# USB-to-Quad-RS-485-Conv-Module.net
KiCad netlist of a schematic drawn in EAGLE
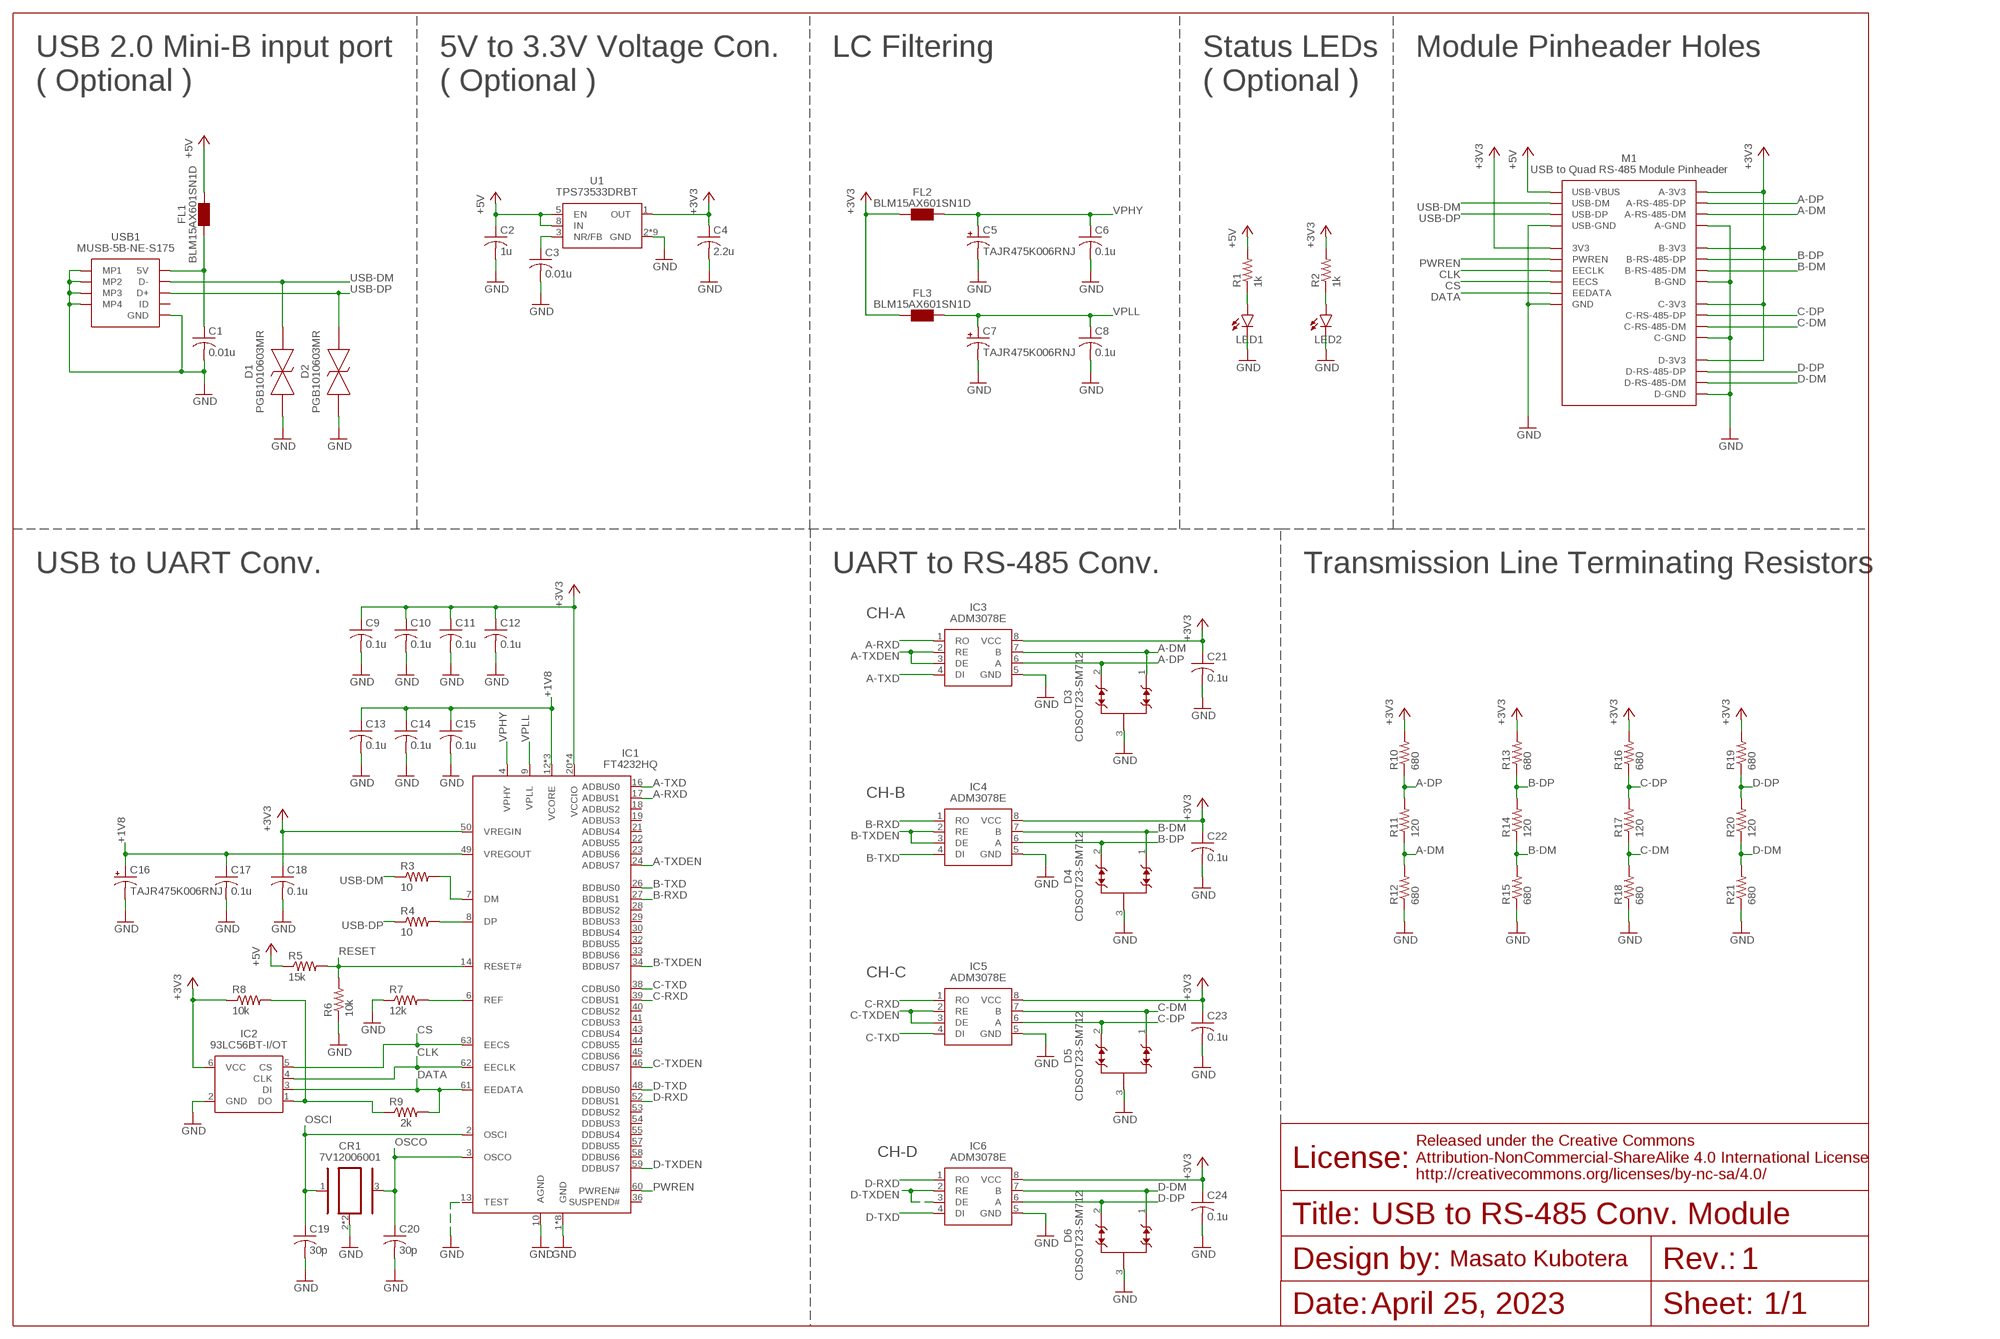
[diagram p0: schematic, sheet 1]

(export (version "E")
  (design (tool "Eeschema 10.0.6"))
  (components
    (comp (ref "C1")
      (value "0.01u")
      (footprint "eagle-import:C0402")
      (libsource (lib "eagle-import") (part "C-USC0402"))
    )
    (comp (ref "C2")
      (value "1u")
      (footprint "eagle-import:C0402")
      (libsource (lib "eagle-import") (part "C-USC0402"))
    )
    (comp (ref "C3")
      (value "0.01u")
      (footprint "eagle-import:C0402")
      (libsource (lib "eagle-import") (part "C-USC0402"))
    )
    (comp (ref "C4")
      (value "2.2u")
      (footprint "eagle-import:C0402")
      (libsource (lib "eagle-import") (part "C-USC0402"))
    )
    (comp (ref "C5")
      (value "4.7u")
      (footprint "eagle-import:0805K")
      (libsource (lib "eagle-import") (part "TAJR475K006RNJ"))
    )
    (comp (ref "C6")
      (value "0.1u")
      (footprint "eagle-import:C0402")
      (libsource (lib "eagle-import") (part "C-USC0402"))
    )
    (comp (ref "C7")
      (value "4.7u")
      (footprint "eagle-import:0805K")
      (libsource (lib "eagle-import") (part "TAJR475K006RNJ"))
    )
    (comp (ref "C8")
      (value "0.1u")
      (footprint "eagle-import:C0402")
      (libsource (lib "eagle-import") (part "C-USC0402"))
    )
    (comp (ref "C9")
      (value "0.1u")
      (footprint "eagle-import:C0402")
      (libsource (lib "eagle-import") (part "C-USC0402"))
    )
    (comp (ref "C10")
      (value "0.1u")
      (footprint "eagle-import:C0402")
      (libsource (lib "eagle-import") (part "C-USC0402"))
    )
    (comp (ref "C11")
      (value "0.1u")
      (footprint "eagle-import:C0402")
      (libsource (lib "eagle-import") (part "C-USC0402"))
    )
    (comp (ref "C12")
      (value "0.1u")
      (footprint "eagle-import:C0402")
      (libsource (lib "eagle-import") (part "C-USC0402"))
    )
    (comp (ref "C13")
      (value "0.1u")
      (footprint "eagle-import:C0402")
      (libsource (lib "eagle-import") (part "C-USC0402"))
    )
    (comp (ref "C14")
      (value "0.1u")
      (footprint "eagle-import:C0402")
      (libsource (lib "eagle-import") (part "C-USC0402"))
    )
    (comp (ref "C15")
      (value "0.1u")
      (footprint "eagle-import:C0402")
      (libsource (lib "eagle-import") (part "C-USC0402"))
    )
    (comp (ref "C16")
      (value "4.7u")
      (footprint "eagle-import:0805K")
      (libsource (lib "eagle-import") (part "TAJR475K006RNJ"))
    )
    (comp (ref "C17")
      (value "0.1u")
      (footprint "eagle-import:C0402")
      (libsource (lib "eagle-import") (part "C-USC0402"))
    )
    (comp (ref "C18")
      (value "0.1u")
      (footprint "eagle-import:C0402")
      (libsource (lib "eagle-import") (part "C-USC0402"))
    )
    (comp (ref "C19")
      (value "30p")
      (footprint "eagle-import:C0402")
      (libsource (lib "eagle-import") (part "C-USC0402"))
    )
    (comp (ref "C20")
      (value "30p")
      (footprint "eagle-import:C0402")
      (libsource (lib "eagle-import") (part "C-USC0402"))
    )
    (comp (ref "C21")
      (value "0.1u")
      (footprint "eagle-import:C0402")
      (libsource (lib "eagle-import") (part "C-USC0402"))
    )
    (comp (ref "C22")
      (value "0.1u")
      (footprint "eagle-import:C0402")
      (libsource (lib "eagle-import") (part "C-USC0402"))
    )
    (comp (ref "C23")
      (value "0.1u")
      (footprint "eagle-import:C0402")
      (libsource (lib "eagle-import") (part "C-USC0402"))
    )
    (comp (ref "C24")
      (value "0.1u")
      (footprint "eagle-import:C0402")
      (libsource (lib "eagle-import") (part "C-USC0402"))
    )
    (comp (ref "CR1")
      (value "7V12006001")
      (footprint "eagle-import:7V12006001")
      (libsource (lib "eagle-import") (part "7V12006001"))
    )
    (comp (ref "D1")
      (value "PGB1010603MR")
      (footprint "eagle-import:0603")
      (libsource (lib "eagle-import") (part "PGB1010603MR"))
    )
    (comp (ref "D2")
      (value "PGB1010603MR")
      (footprint "eagle-import:0603")
      (libsource (lib "eagle-import") (part "PGB1010603MR"))
    )
    (comp (ref "D3")
      (value "CDSOT23-SM712")
      (footprint "eagle-import:SOT-23-3")
      (libsource (lib "eagle-import") (part "CDSOT23-SM712"))
    )
    (comp (ref "D4")
      (value "CDSOT23-SM712")
      (footprint "eagle-import:SOT-23-3")
      (libsource (lib "eagle-import") (part "CDSOT23-SM712"))
    )
    (comp (ref "D5")
      (value "CDSOT23-SM712")
      (footprint "eagle-import:SOT-23-3")
      (libsource (lib "eagle-import") (part "CDSOT23-SM712"))
    )
    (comp (ref "D6")
      (value "CDSOT23-SM712")
      (footprint "eagle-import:SOT-23-3")
      (libsource (lib "eagle-import") (part "CDSOT23-SM712"))
    )
    (comp (ref "FL1")
      (value "BLM15AX601SN1D")
      (footprint "eagle-import:BLM15AX601SN1D")
      (libsource (lib "eagle-import") (part "BLM15AX601SN1D"))
    )
    (comp (ref "FL2")
      (value "BLM15AX601SN1D")
      (footprint "eagle-import:BLM15AX601SN1D")
      (libsource (lib "eagle-import") (part "BLM15AX601SN1D"))
    )
    (comp (ref "FL3")
      (value "BLM15AX601SN1D")
      (footprint "eagle-import:BLM15AX601SN1D")
      (libsource (lib "eagle-import") (part "BLM15AX601SN1D"))
    )
    (comp (ref "IC1")
      (value "FT4232HQ")
      (footprint "eagle-import:FT4232HQ")
      (libsource (lib "eagle-import") (part "FT4232HQ"))
    )
    (comp (ref "IC2")
      (value "93LC56BT-I/OT")
      (footprint "eagle-import:SOT-23-6")
      (libsource (lib "eagle-import") (part "93LC56BT-I/OT"))
    )
    (comp (ref "IC3")
      (value "ADM3078E")
      (footprint "eagle-import:SOIC-8")
      (libsource (lib "eagle-import") (part "ADM3078E"))
    )
    (comp (ref "IC4")
      (value "ADM3078E")
      (footprint "eagle-import:SOIC-8")
      (libsource (lib "eagle-import") (part "ADM3078E"))
    )
    (comp (ref "IC5")
      (value "ADM3078E")
      (footprint "eagle-import:SOIC-8")
      (libsource (lib "eagle-import") (part "ADM3078E"))
    )
    (comp (ref "IC6")
      (value "ADM3078E")
      (footprint "eagle-import:SOIC-8")
      (libsource (lib "eagle-import") (part "ADM3078E"))
    )
    (comp (ref "LED1")
      (value "LEDSML0603")
      (footprint "eagle-import:SML0603")
      (libsource (lib "eagle-import") (part "LEDSML0603"))
    )
    (comp (ref "LED2")
      (value "LEDSML0603")
      (footprint "eagle-import:SML0603")
      (libsource (lib "eagle-import") (part "LEDSML0603"))
    )
    (comp (ref "M1")
      (value "USB-TO-QUAD-RS-485-CONV-MODULE")
      (footprint "eagle-import:USB-TO-QUAD-RS-485-CONV-MODULE-DIMENSION")
      (libsource (lib "eagle-import") (part "USB-TO-QUAD-RS-485-CONV-MODULE"))
    )
    (comp (ref "R1")
      (value "1k")
      (footprint "eagle-import:R0402")
      (libsource (lib "eagle-import") (part "R-US_R0402"))
    )
    (comp (ref "R2")
      (value "1k")
      (footprint "eagle-import:R0402")
      (libsource (lib "eagle-import") (part "R-US_R0402"))
    )
    (comp (ref "R3")
      (value "10")
      (footprint "eagle-import:R0402")
      (libsource (lib "eagle-import") (part "R-US_R0402"))
    )
    (comp (ref "R4")
      (value "10")
      (footprint "eagle-import:R0402")
      (libsource (lib "eagle-import") (part "R-US_R0402"))
    )
    (comp (ref "R5")
      (value "15k")
      (footprint "eagle-import:R0402")
      (libsource (lib "eagle-import") (part "R-US_R0402"))
    )
    (comp (ref "R6")
      (value "10k")
      (footprint "eagle-import:R0402")
      (libsource (lib "eagle-import") (part "R-US_R0402"))
    )
    (comp (ref "R7")
      (value "12k")
      (footprint "eagle-import:R0402")
      (libsource (lib "eagle-import") (part "R-US_R0402"))
    )
    (comp (ref "R8")
      (value "10k")
      (footprint "eagle-import:R0402")
      (libsource (lib "eagle-import") (part "R-US_R0402"))
    )
    (comp (ref "R9")
      (value "2k")
      (footprint "eagle-import:R0402")
      (libsource (lib "eagle-import") (part "R-US_R0402"))
    )
    (comp (ref "R10")
      (value "680")
      (footprint "eagle-import:R0402")
      (libsource (lib "eagle-import") (part "R-US_R0402"))
    )
    (comp (ref "R11")
      (value "120")
      (footprint "eagle-import:R0402")
      (libsource (lib "eagle-import") (part "R-US_R0402"))
    )
    (comp (ref "R12")
      (value "680")
      (footprint "eagle-import:R0402")
      (libsource (lib "eagle-import") (part "R-US_R0402"))
    )
    (comp (ref "R13")
      (value "680")
      (footprint "eagle-import:R0402")
      (libsource (lib "eagle-import") (part "R-US_R0402"))
    )
    (comp (ref "R14")
      (value "120")
      (footprint "eagle-import:R0402")
      (libsource (lib "eagle-import") (part "R-US_R0402"))
    )
    (comp (ref "R15")
      (value "680")
      (footprint "eagle-import:R0402")
      (libsource (lib "eagle-import") (part "R-US_R0402"))
    )
    (comp (ref "R16")
      (value "680")
      (footprint "eagle-import:R0402")
      (libsource (lib "eagle-import") (part "R-US_R0402"))
    )
    (comp (ref "R17")
      (value "120")
      (footprint "eagle-import:R0402")
      (libsource (lib "eagle-import") (part "R-US_R0402"))
    )
    (comp (ref "R18")
      (value "680")
      (footprint "eagle-import:R0402")
      (libsource (lib "eagle-import") (part "R-US_R0402"))
    )
    (comp (ref "R19")
      (value "680")
      (footprint "eagle-import:R0402")
      (libsource (lib "eagle-import") (part "R-US_R0402"))
    )
    (comp (ref "R20")
      (value "120")
      (footprint "eagle-import:R0402")
      (libsource (lib "eagle-import") (part "R-US_R0402"))
    )
    (comp (ref "R21")
      (value "680")
      (footprint "eagle-import:R0402")
      (libsource (lib "eagle-import") (part "R-US_R0402"))
    )
    (comp (ref "U1")
      (value "TPS73533DRBT")
      (footprint "eagle-import:SON-8")
      (libsource (lib "eagle-import") (part "TPS73533DRBT"))
    )
    (comp (ref "USB1")
      (value "MINI_USB_B_SMD")
      (footprint "eagle-import:MINI_USB_B_SMD")
      (libsource (lib "eagle-import") (part "MINI_USB_B_SMD"))
    )
  )
  (nets
    (net (code "1") (name "+3V3") (class "Default")
      (node (ref "C10") (pin "1") (pinfunction "1_1") (pintype "passive"))
      (node (ref "C11") (pin "1") (pinfunction "1_1") (pintype "passive"))
      (node (ref "C12") (pin "1") (pinfunction "1_1") (pintype "passive"))
      (node (ref "C18") (pin "1") (pinfunction "1_1") (pintype "passive"))
      (node (ref "C21") (pin "1") (pinfunction "1_1") (pintype "passive"))
      (node (ref "C22") (pin "1") (pinfunction "1_1") (pintype "passive"))
      (node (ref "C23") (pin "1") (pinfunction "1_1") (pintype "passive"))
      (node (ref "C24") (pin "1") (pinfunction "1_1") (pintype "passive"))
      (node (ref "C4") (pin "1") (pinfunction "1_1") (pintype "passive"))
      (node (ref "C9") (pin "1") (pinfunction "1_1") (pintype "passive"))
      (node (ref "FL2") (pin "1") (pinfunction "1_1") (pintype "bidirectional"))
      (node (ref "FL3") (pin "1") (pinfunction "1_1") (pintype "bidirectional"))
      (node (ref "IC1") (pin "20") (pinfunction "VCCIO_20") (pintype "bidirectional"))
      (node (ref "IC1") (pin "31") (pinfunction "VCCIO_31") (pintype "bidirectional"))
      (node (ref "IC1") (pin "42") (pinfunction "VCCIO_42") (pintype "bidirectional"))
      (node (ref "IC1") (pin "50") (pinfunction "VREGIN_50") (pintype "bidirectional"))
      (node (ref "IC1") (pin "56") (pinfunction "VCCIO_56") (pintype "bidirectional"))
      (node (ref "IC2") (pin "6") (pinfunction "VCC_6") (pintype "bidirectional"))
      (node (ref "IC3") (pin "8") (pinfunction "VCC_8") (pintype "power_in"))
      (node (ref "IC4") (pin "8") (pinfunction "VCC_8") (pintype "power_in"))
      (node (ref "IC5") (pin "8") (pinfunction "VCC_8") (pintype "power_in"))
      (node (ref "IC6") (pin "8") (pinfunction "VCC_8") (pintype "power_in"))
      (node (ref "M1") (pin "3V3") (pinfunction "3V3_3V3") (pintype "bidirectional"))
      (node (ref "M1") (pin "A-3V3") (pinfunction "A-3V3_A-3V3") (pintype "bidirectional"))
      (node (ref "M1") (pin "B-3.3V") (pinfunction "B-3V3_B-3.3V") (pintype "bidirectional"))
      (node (ref "M1") (pin "C-3V3") (pinfunction "C-3V3_C-3V3") (pintype "bidirectional"))
      (node (ref "M1") (pin "D-3V3") (pinfunction "D-3V3_D-3V3") (pintype "bidirectional"))
      (node (ref "R10") (pin "2") (pinfunction "2_2") (pintype "passive"))
      (node (ref "R13") (pin "2") (pinfunction "2_2") (pintype "passive"))
      (node (ref "R16") (pin "2") (pinfunction "2_2") (pintype "passive"))
      (node (ref "R19") (pin "2") (pinfunction "2_2") (pintype "passive"))
      (node (ref "R2") (pin "2") (pinfunction "2_2") (pintype "passive"))
      (node (ref "R8") (pin "1") (pinfunction "1_1") (pintype "passive"))
      (node (ref "U1") (pin "1") (pinfunction "OUT_1") (pintype "output"))
    )
    (net (code "2") (name "+5V") (class "Default")
      (node (ref "C2") (pin "1") (pinfunction "1_1") (pintype "passive"))
      (node (ref "FL1") (pin "2") (pinfunction "2_2") (pintype "bidirectional"))
      (node (ref "M1") (pin "USB-VBUS") (pinfunction "USB-VBUS_USB-VBUS") (pintype "bidirectional"))
      (node (ref "R1") (pin "2") (pinfunction "2_2") (pintype "passive"))
      (node (ref "R5") (pin "1") (pinfunction "1_1") (pintype "passive"))
      (node (ref "U1") (pin "5") (pinfunction "EN_5") (pintype "input"))
      (node (ref "U1") (pin "8") (pinfunction "IN_8") (pintype "input"))
    )
    (net (code "3") (name "/+1V8") (class "Default")
      (node (ref "C13") (pin "1") (pinfunction "1_1") (pintype "passive"))
      (node (ref "C14") (pin "1") (pinfunction "1_1") (pintype "passive"))
      (node (ref "C15") (pin "1") (pinfunction "1_1") (pintype "passive"))
      (node (ref "C16") (pin "1") (pinfunction "+_1") (pintype "passive"))
      (node (ref "C17") (pin "1") (pinfunction "1_1") (pintype "passive"))
      (node (ref "IC1") (pin "12") (pinfunction "VCORE_12") (pintype "bidirectional"))
      (node (ref "IC1") (pin "37") (pinfunction "VCORE_37") (pintype "bidirectional"))
      (node (ref "IC1") (pin "49") (pinfunction "VREGOUT_49") (pintype "bidirectional"))
      (node (ref "IC1") (pin "64") (pinfunction "VCORE_64") (pintype "bidirectional"))
    )
    (net (code "4") (name "/A-DM") (class "Default")
      (node (ref "D3") (pin "1") (pinfunction "1_1") (pintype "bidirectional"))
      (node (ref "IC3") (pin "7") (pinfunction "B_7") (pintype "bidirectional"))
      (node (ref "M1") (pin "A-RS-485-DM") (pinfunction "A-RS-485-DM_A-RS-485-DM") (pintype "bidirectional"))
      (node (ref "R11") (pin "1") (pinfunction "1_1") (pintype "passive"))
      (node (ref "R12") (pin "2") (pinfunction "2_2") (pintype "passive"))
    )
    (net (code "5") (name "/A-DP") (class "Default")
      (node (ref "D3") (pin "2") (pinfunction "2_2") (pintype "bidirectional"))
      (node (ref "IC3") (pin "6") (pinfunction "A_6") (pintype "bidirectional"))
      (node (ref "M1") (pin "A-RS-485-DP") (pinfunction "A-RS-485-DP_A-RS-485-DP") (pintype "bidirectional"))
      (node (ref "R10") (pin "1") (pinfunction "1_1") (pintype "passive"))
      (node (ref "R11") (pin "2") (pinfunction "2_2") (pintype "passive"))
    )
    (net (code "6") (name "/A-RXD") (class "Default")
      (node (ref "IC1") (pin "17") (pinfunction "ADBUS1_17") (pintype "bidirectional"))
      (node (ref "IC3") (pin "1") (pinfunction "RO_1") (pintype "bidirectional"))
    )
    (net (code "7") (name "/A-TXD") (class "Default")
      (node (ref "IC1") (pin "16") (pinfunction "ADBUS0_16") (pintype "bidirectional"))
      (node (ref "IC3") (pin "4") (pinfunction "DI_4") (pintype "bidirectional"))
    )
    (net (code "8") (name "/A-TXDEN") (class "Default")
      (node (ref "IC1") (pin "24") (pinfunction "ADBUS7_24") (pintype "bidirectional"))
      (node (ref "IC3") (pin "2") (pinfunction "RE_2") (pintype "bidirectional"))
      (node (ref "IC3") (pin "3") (pinfunction "DE_3") (pintype "bidirectional"))
    )
    (net (code "9") (name "/B-DM") (class "Default")
      (node (ref "D4") (pin "1") (pinfunction "1_1") (pintype "bidirectional"))
      (node (ref "IC4") (pin "7") (pinfunction "B_7") (pintype "bidirectional"))
      (node (ref "M1") (pin "B-RS-485-DM") (pinfunction "B-RS-485-DM_B-RS-485-DM") (pintype "bidirectional"))
      (node (ref "R14") (pin "1") (pinfunction "1_1") (pintype "passive"))
      (node (ref "R15") (pin "2") (pinfunction "2_2") (pintype "passive"))
    )
    (net (code "10") (name "/B-DP") (class "Default")
      (node (ref "D4") (pin "2") (pinfunction "2_2") (pintype "bidirectional"))
      (node (ref "IC4") (pin "6") (pinfunction "A_6") (pintype "bidirectional"))
      (node (ref "M1") (pin "B-RS-485-DP") (pinfunction "B-RS-485-DP_B-RS-485-DP") (pintype "bidirectional"))
      (node (ref "R13") (pin "1") (pinfunction "1_1") (pintype "passive"))
      (node (ref "R14") (pin "2") (pinfunction "2_2") (pintype "passive"))
    )
    (net (code "11") (name "/B-RXD") (class "Default")
      (node (ref "IC1") (pin "27") (pinfunction "BDBUS1_27") (pintype "bidirectional"))
      (node (ref "IC4") (pin "1") (pinfunction "RO_1") (pintype "bidirectional"))
    )
    (net (code "12") (name "/B-TXD") (class "Default")
      (node (ref "IC1") (pin "26") (pinfunction "BDBUS0_26") (pintype "bidirectional"))
      (node (ref "IC4") (pin "4") (pinfunction "DI_4") (pintype "bidirectional"))
    )
    (net (code "13") (name "/B-TXDEN") (class "Default")
      (node (ref "IC1") (pin "34") (pinfunction "BDBUS7_34") (pintype "bidirectional"))
      (node (ref "IC4") (pin "2") (pinfunction "RE_2") (pintype "bidirectional"))
      (node (ref "IC4") (pin "3") (pinfunction "DE_3") (pintype "bidirectional"))
    )
    (net (code "14") (name "/C-DM") (class "Default")
      (node (ref "D5") (pin "1") (pinfunction "1_1") (pintype "bidirectional"))
      (node (ref "IC5") (pin "7") (pinfunction "B_7") (pintype "bidirectional"))
      (node (ref "M1") (pin "C-RS-485-DM") (pinfunction "C-RS-485-DM_C-RS-485-DM") (pintype "bidirectional"))
      (node (ref "R17") (pin "1") (pinfunction "1_1") (pintype "passive"))
      (node (ref "R18") (pin "2") (pinfunction "2_2") (pintype "passive"))
    )
    (net (code "15") (name "/C-DP") (class "Default")
      (node (ref "D5") (pin "2") (pinfunction "2_2") (pintype "bidirectional"))
      (node (ref "IC5") (pin "6") (pinfunction "A_6") (pintype "bidirectional"))
      (node (ref "M1") (pin "C-RS-485-DP") (pinfunction "C-RS-485-DP_C-RS-485-DP") (pintype "bidirectional"))
      (node (ref "R16") (pin "1") (pinfunction "1_1") (pintype "passive"))
      (node (ref "R17") (pin "2") (pinfunction "2_2") (pintype "passive"))
    )
    (net (code "16") (name "/C-RXD") (class "Default")
      (node (ref "IC1") (pin "39") (pinfunction "CDBUS1_39") (pintype "bidirectional"))
      (node (ref "IC5") (pin "1") (pinfunction "RO_1") (pintype "bidirectional"))
    )
    (net (code "17") (name "/C-TXD") (class "Default")
      (node (ref "IC1") (pin "38") (pinfunction "CDBUS0_38") (pintype "bidirectional"))
      (node (ref "IC5") (pin "4") (pinfunction "DI_4") (pintype "bidirectional"))
    )
    (net (code "18") (name "/C-TXDEN") (class "Default")
      (node (ref "IC1") (pin "46") (pinfunction "CDBUS7_46") (pintype "bidirectional"))
      (node (ref "IC5") (pin "2") (pinfunction "RE_2") (pintype "bidirectional"))
      (node (ref "IC5") (pin "3") (pinfunction "DE_3") (pintype "bidirectional"))
    )
    (net (code "19") (name "/CLK") (class "Default")
      (node (ref "IC1") (pin "62") (pinfunction "EECLK_62") (pintype "bidirectional"))
      (node (ref "IC2") (pin "4") (pinfunction "CLK_4") (pintype "bidirectional"))
      (node (ref "M1") (pin "EECLK") (pinfunction "EECLK_EECLK") (pintype "bidirectional"))
    )
    (net (code "20") (name "/CS") (class "Default")
      (node (ref "IC1") (pin "63") (pinfunction "EECS_63") (pintype "bidirectional"))
      (node (ref "IC2") (pin "5") (pinfunction "CS_5") (pintype "bidirectional"))
      (node (ref "M1") (pin "EECS") (pinfunction "EECS_EECS") (pintype "bidirectional"))
    )
    (net (code "21") (name "/D-DM") (class "Default")
      (node (ref "D6") (pin "1") (pinfunction "1_1") (pintype "bidirectional"))
      (node (ref "IC6") (pin "7") (pinfunction "B_7") (pintype "bidirectional"))
      (node (ref "M1") (pin "D-RS-485-DM") (pinfunction "D-RS-485-DM_D-RS-485-DM") (pintype "bidirectional"))
      (node (ref "R20") (pin "1") (pinfunction "1_1") (pintype "passive"))
      (node (ref "R21") (pin "2") (pinfunction "2_2") (pintype "passive"))
    )
    (net (code "22") (name "/D-DP") (class "Default")
      (node (ref "D6") (pin "2") (pinfunction "2_2") (pintype "bidirectional"))
      (node (ref "IC6") (pin "6") (pinfunction "A_6") (pintype "bidirectional"))
      (node (ref "M1") (pin "D-RS-485-DP") (pinfunction "D-RS-485-DP_D-RS-485-DP") (pintype "bidirectional"))
      (node (ref "R19") (pin "1") (pinfunction "1_1") (pintype "passive"))
      (node (ref "R20") (pin "2") (pinfunction "2_2") (pintype "passive"))
    )
    (net (code "23") (name "/D-RXD") (class "Default")
      (node (ref "IC1") (pin "52") (pinfunction "DDBUS1_52") (pintype "bidirectional"))
      (node (ref "IC6") (pin "1") (pinfunction "RO_1") (pintype "bidirectional"))
    )
    (net (code "24") (name "/D-TXD") (class "Default")
      (node (ref "IC1") (pin "48") (pinfunction "DDBUS0_48") (pintype "bidirectional"))
      (node (ref "IC6") (pin "4") (pinfunction "DI_4") (pintype "bidirectional"))
    )
    (net (code "25") (name "/D-TXDEN") (class "Default")
      (node (ref "IC1") (pin "59") (pinfunction "DDBUS7_59") (pintype "bidirectional"))
      (node (ref "IC6") (pin "2") (pinfunction "RE_2") (pintype "bidirectional"))
      (node (ref "IC6") (pin "3") (pinfunction "DE_3") (pintype "bidirectional"))
    )
    (net (code "26") (name "/DATA") (class "Default")
      (node (ref "IC1") (pin "61") (pinfunction "EEDATA_61") (pintype "bidirectional"))
      (node (ref "IC2") (pin "3") (pinfunction "DI_3") (pintype "bidirectional"))
      (node (ref "M1") (pin "EEDATA") (pinfunction "EEDATA_EEDATA") (pintype "bidirectional"))
      (node (ref "R9") (pin "2") (pinfunction "2_2") (pintype "passive"))
    )
    (net (code "27") (name "/OSCI") (class "Default")
      (node (ref "C19") (pin "1") (pinfunction "1_1") (pintype "passive"))
      (node (ref "CR1") (pin "1") (pinfunction "P$1_1") (pintype "bidirectional"))
      (node (ref "IC1") (pin "2") (pinfunction "OSCI_2") (pintype "bidirectional"))
    )
    (net (code "28") (name "/OSCO") (class "Default")
      (node (ref "C20") (pin "1") (pinfunction "1_1") (pintype "passive"))
      (node (ref "CR1") (pin "3") (pinfunction "P$2_3") (pintype "bidirectional"))
      (node (ref "IC1") (pin "3") (pinfunction "OSCO_3") (pintype "bidirectional"))
    )
    (net (code "29") (name "/PWREN") (class "Default")
      (node (ref "IC1") (pin "60") (pinfunction "PWREN#_60") (pintype "bidirectional"))
      (node (ref "M1") (pin "PWREN") (pinfunction "PWREN_PWREN") (pintype "bidirectional"))
    )
    (net (code "30") (name "/RESET") (class "Default")
      (node (ref "IC1") (pin "14") (pinfunction "RESET#_14") (pintype "bidirectional"))
      (node (ref "R5") (pin "2") (pinfunction "2_2") (pintype "passive"))
      (node (ref "R6") (pin "2") (pinfunction "2_2") (pintype "passive"))
    )
    (net (code "31") (name "/USB-DM") (class "Default")
      (node (ref "D1") (pin "2") (pinfunction "2_2") (pintype "bidirectional"))
      (node (ref "M1") (pin "USB-DM") (pinfunction "USB-DM_USB-DM") (pintype "bidirectional"))
      (node (ref "R3") (pin "1") (pinfunction "1_1") (pintype "passive"))
      (node (ref "USB1") (pin "2") (pinfunction "D-_2") (pintype "bidirectional"))
    )
    (net (code "32") (name "/USB-DP") (class "Default")
      (node (ref "D2") (pin "2") (pinfunction "2_2") (pintype "bidirectional"))
      (node (ref "M1") (pin "USB-DP") (pinfunction "USB-DP_USB-DP") (pintype "bidirectional"))
      (node (ref "R4") (pin "1") (pinfunction "1_1") (pintype "passive"))
      (node (ref "USB1") (pin "3") (pinfunction "D+_3") (pintype "bidirectional"))
    )
    (net (code "33") (name "/VPHY") (class "Default")
      (node (ref "C5") (pin "1") (pinfunction "+_1") (pintype "passive"))
      (node (ref "C6") (pin "1") (pinfunction "1_1") (pintype "passive"))
      (node (ref "FL2") (pin "2") (pinfunction "2_2") (pintype "bidirectional"))
      (node (ref "IC1") (pin "4") (pinfunction "VPHY_4") (pintype "bidirectional"))
    )
    (net (code "34") (name "/VPLL") (class "Default")
      (node (ref "C7") (pin "1") (pinfunction "+_1") (pintype "passive"))
      (node (ref "C8") (pin "1") (pinfunction "1_1") (pintype "passive"))
      (node (ref "FL3") (pin "2") (pinfunction "2_2") (pintype "bidirectional"))
      (node (ref "IC1") (pin "9") (pinfunction "VPLL_9") (pintype "bidirectional"))
    )
    (net (code "35") (name "GND") (class "Default")
      (node (ref "C1") (pin "2") (pinfunction "2_2") (pintype "passive"))
      (node (ref "C10") (pin "2") (pinfunction "2_2") (pintype "passive"))
      (node (ref "C11") (pin "2") (pinfunction "2_2") (pintype "passive"))
      (node (ref "C12") (pin "2") (pinfunction "2_2") (pintype "passive"))
      (node (ref "C13") (pin "2") (pinfunction "2_2") (pintype "passive"))
      (node (ref "C14") (pin "2") (pinfunction "2_2") (pintype "passive"))
      (node (ref "C15") (pin "2") (pinfunction "2_2") (pintype "passive"))
      (node (ref "C16") (pin "2") (pinfunction "-_2") (pintype "passive"))
      (node (ref "C17") (pin "2") (pinfunction "2_2") (pintype "passive"))
      (node (ref "C18") (pin "2") (pinfunction "2_2") (pintype "passive"))
      (node (ref "C19") (pin "2") (pinfunction "2_2") (pintype "passive"))
      (node (ref "C2") (pin "2") (pinfunction "2_2") (pintype "passive"))
      (node (ref "C20") (pin "2") (pinfunction "2_2") (pintype "passive"))
      (node (ref "C21") (pin "2") (pinfunction "2_2") (pintype "passive"))
      (node (ref "C22") (pin "2") (pinfunction "2_2") (pintype "passive"))
      (node (ref "C23") (pin "2") (pinfunction "2_2") (pintype "passive"))
      (node (ref "C24") (pin "2") (pinfunction "2_2") (pintype "passive"))
      (node (ref "C3") (pin "2") (pinfunction "2_2") (pintype "passive"))
      (node (ref "C4") (pin "2") (pinfunction "2_2") (pintype "passive"))
      (node (ref "C5") (pin "2") (pinfunction "-_2") (pintype "passive"))
      (node (ref "C6") (pin "2") (pinfunction "2_2") (pintype "passive"))
      (node (ref "C7") (pin "2") (pinfunction "-_2") (pintype "passive"))
      (node (ref "C8") (pin "2") (pinfunction "2_2") (pintype "passive"))
      (node (ref "C9") (pin "2") (pinfunction "2_2") (pintype "passive"))
      (node (ref "CR1") (pin "2") (pinfunction "P$3_2") (pintype "bidirectional"))
      (node (ref "CR1") (pin "4") (pinfunction "P$3_4") (pintype "bidirectional"))
      (node (ref "D1") (pin "1") (pinfunction "1_1") (pintype "bidirectional"))
      (node (ref "D2") (pin "1") (pinfunction "1_1") (pintype "bidirectional"))
      (node (ref "D3") (pin "3") (pinfunction "3_3") (pintype "bidirectional"))
      (node (ref "D4") (pin "3") (pinfunction "3_3") (pintype "bidirectional"))
      (node (ref "D5") (pin "3") (pinfunction "3_3") (pintype "bidirectional"))
      (node (ref "D6") (pin "3") (pinfunction "3_3") (pintype "bidirectional"))
      (node (ref "IC1") (pin "1") (pinfunction "GND_1") (pintype "bidirectional"))
      (node (ref "IC1") (pin "10") (pinfunction "AGND_10") (pintype "bidirectional"))
      (node (ref "IC1") (pin "11") (pinfunction "GND_11") (pintype "bidirectional"))
      (node (ref "IC1") (pin "13") (pinfunction "TEST_13") (pintype "bidirectional"))
      (node (ref "IC1") (pin "15") (pinfunction "GND_15") (pintype "bidirectional"))
      (node (ref "IC1") (pin "25") (pinfunction "GND_25") (pintype "bidirectional"))
      (node (ref "IC1") (pin "35") (pinfunction "GND_35") (pintype "bidirectional"))
      (node (ref "IC1") (pin "47") (pinfunction "GND_47") (pintype "bidirectional"))
      (node (ref "IC1") (pin "5") (pinfunction "GND_5") (pintype "bidirectional"))
      (node (ref "IC1") (pin "51") (pinfunction "GND_51") (pintype "bidirectional"))
      (node (ref "IC2") (pin "2") (pinfunction "GND_2") (pintype "bidirectional"))
      (node (ref "IC3") (pin "5") (pinfunction "GND_5") (pintype "power_in"))
      (node (ref "IC4") (pin "5") (pinfunction "GND_5") (pintype "power_in"))
      (node (ref "IC5") (pin "5") (pinfunction "GND_5") (pintype "power_in"))
      (node (ref "IC6") (pin "5") (pinfunction "GND_5") (pintype "power_in"))
      (node (ref "LED1") (pin "C") (pinfunction "C_C") (pintype "passive"))
      (node (ref "LED2") (pin "C") (pinfunction "C_C") (pintype "passive"))
      (node (ref "M1") (pin "A-GND") (pinfunction "A-GND_A-GND") (pintype "bidirectional"))
      (node (ref "M1") (pin "B-GND") (pinfunction "B-GND_B-GND") (pintype "bidirectional"))
      (node (ref "M1") (pin "C-GND") (pinfunction "C-GND_C-GND") (pintype "bidirectional"))
      (node (ref "M1") (pin "D-GND") (pinfunction "D-GND_D-GND") (pintype "bidirectional"))
      (node (ref "M1") (pin "GND1") (pinfunction "GND_GND1") (pintype "bidirectional"))
      (node (ref "M1") (pin "USB-GND") (pinfunction "USB-GND_USB-GND") (pintype "bidirectional"))
      (node (ref "R12") (pin "1") (pinfunction "1_1") (pintype "passive"))
      (node (ref "R15") (pin "1") (pinfunction "1_1") (pintype "passive"))
      (node (ref "R18") (pin "1") (pinfunction "1_1") (pintype "passive"))
      (node (ref "R21") (pin "1") (pinfunction "1_1") (pintype "passive"))
      (node (ref "R6") (pin "1") (pinfunction "1_1") (pintype "passive"))
      (node (ref "R7") (pin "1") (pinfunction "1_1") (pintype "passive"))
      (node (ref "U1") (pin "10") (pinfunction "GND_10") (pintype "power_in"))
      (node (ref "U1") (pin "11") (pinfunction "GND_11") (pintype "power_in"))
      (node (ref "U1") (pin "12") (pinfunction "GND_12") (pintype "power_in"))
      (node (ref "U1") (pin "13") (pinfunction "GND_13") (pintype "power_in"))
      (node (ref "U1") (pin "2") (pinfunction "GND_2") (pintype "power_in"))
      (node (ref "U1") (pin "4") (pinfunction "GND_4") (pintype "power_in"))
      (node (ref "U1") (pin "6") (pinfunction "GND_6") (pintype "power_in"))
      (node (ref "U1") (pin "7") (pinfunction "GND_7") (pintype "power_in"))
      (node (ref "U1") (pin "9") (pinfunction "GND_9") (pintype "power_in"))
      (node (ref "USB1") (pin "5") (pinfunction "GND_5") (pintype "bidirectional"))
      (node (ref "USB1") (pin "MP1") (pinfunction "MP1_MP1") (pintype "bidirectional"))
      (node (ref "USB1") (pin "MP2") (pinfunction "MP2_MP2") (pintype "bidirectional"))
      (node (ref "USB1") (pin "MP3") (pinfunction "MP3_MP3") (pintype "bidirectional"))
      (node (ref "USB1") (pin "MP4") (pinfunction "MP4_MP4") (pintype "bidirectional"))
    )
    (net (code "36") (name "Net-(IC1-DM)") (class "Default")
      (node (ref "IC1") (pin "7") (pinfunction "DM_7") (pintype "bidirectional"))
      (node (ref "R3") (pin "2") (pinfunction "2_2") (pintype "passive"))
    )
    (net (code "37") (name "Net-(IC1-DP)") (class "Default")
      (node (ref "IC1") (pin "8") (pinfunction "DP_8") (pintype "bidirectional"))
      (node (ref "R4") (pin "2") (pinfunction "2_2") (pintype "passive"))
    )
    (net (code "38") (name "Net-(IC1-REF)") (class "Default")
      (node (ref "IC1") (pin "6") (pinfunction "REF_6") (pintype "bidirectional"))
      (node (ref "R7") (pin "2") (pinfunction "2_2") (pintype "passive"))
    )
    (net (code "39") (name "Net-(IC2-DO)") (class "Default")
      (node (ref "IC2") (pin "1") (pinfunction "DO_1") (pintype "bidirectional"))
      (node (ref "R8") (pin "2") (pinfunction "2_2") (pintype "passive"))
      (node (ref "R9") (pin "1") (pinfunction "1_1") (pintype "passive"))
    )
    (net (code "40") (name "Net-(LED1-PadA)") (class "Default")
      (node (ref "LED1") (pin "A") (pinfunction "A_A") (pintype "passive"))
      (node (ref "R1") (pin "1") (pinfunction "1_1") (pintype "passive"))
    )
    (net (code "41") (name "Net-(LED2-PadA)") (class "Default")
      (node (ref "LED2") (pin "A") (pinfunction "A_A") (pintype "passive"))
      (node (ref "R2") (pin "1") (pinfunction "1_1") (pintype "passive"))
    )
    (net (code "42") (name "Net-(U1-NR{slash}FB)") (class "Default")
      (node (ref "C3") (pin "1") (pinfunction "1_1") (pintype "passive"))
      (node (ref "U1") (pin "3") (pinfunction "NR/FB_3") (pintype "input"))
    )
    (net (code "43") (name "Net-(USB1-5V)") (class "Default")
      (node (ref "C1") (pin "1") (pinfunction "1_1") (pintype "passive"))
      (node (ref "FL1") (pin "1") (pinfunction "1_1") (pintype "bidirectional"))
      (node (ref "USB1") (pin "1") (pinfunction "5V_1") (pintype "bidirectional"))
    )
    (net (code "44") (name "unconnected-(IC1-ADBUS2-Pad18)") (class "Default")
      (node (ref "IC1") (pin "18") (pinfunction "ADBUS2_18") (pintype "bidirectional"))
    )
    (net (code "45") (name "unconnected-(IC1-ADBUS3-Pad19)") (class "Default")
      (node (ref "IC1") (pin "19") (pinfunction "ADBUS3_19") (pintype "bidirectional"))
    )
    (net (code "46") (name "unconnected-(IC1-ADBUS4-Pad21)") (class "Default")
      (node (ref "IC1") (pin "21") (pinfunction "ADBUS4_21") (pintype "bidirectional"))
    )
    (net (code "47") (name "unconnected-(IC1-ADBUS5-Pad22)") (class "Default")
      (node (ref "IC1") (pin "22") (pinfunction "ADBUS5_22") (pintype "bidirectional"))
    )
    (net (code "48") (name "unconnected-(IC1-ADBUS6-Pad23)") (class "Default")
      (node (ref "IC1") (pin "23") (pinfunction "ADBUS6_23") (pintype "bidirectional"))
    )
    (net (code "49") (name "unconnected-(IC1-BDBUS2-Pad28)") (class "Default")
      (node (ref "IC1") (pin "28") (pinfunction "BDBUS2_28") (pintype "bidirectional"))
    )
    (net (code "50") (name "unconnected-(IC1-BDBUS3-Pad29)") (class "Default")
      (node (ref "IC1") (pin "29") (pinfunction "BDBUS3_29") (pintype "bidirectional"))
    )
    (net (code "51") (name "unconnected-(IC1-BDBUS4-Pad30)") (class "Default")
      (node (ref "IC1") (pin "30") (pinfunction "BDBUS4_30") (pintype "bidirectional"))
    )
    (net (code "52") (name "unconnected-(IC1-BDBUS5-Pad32)") (class "Default")
      (node (ref "IC1") (pin "32") (pinfunction "BDBUS5_32") (pintype "bidirectional"))
    )
    (net (code "53") (name "unconnected-(IC1-BDBUS6-Pad33)") (class "Default")
      (node (ref "IC1") (pin "33") (pinfunction "BDBUS6_33") (pintype "bidirectional"))
    )
    (net (code "54") (name "unconnected-(IC1-CDBUS2-Pad40)") (class "Default")
      (node (ref "IC1") (pin "40") (pinfunction "CDBUS2_40") (pintype "bidirectional"))
    )
    (net (code "55") (name "unconnected-(IC1-CDBUS3-Pad41)") (class "Default")
      (node (ref "IC1") (pin "41") (pinfunction "CDBUS3_41") (pintype "bidirectional"))
    )
    (net (code "56") (name "unconnected-(IC1-CDBUS4-Pad43)") (class "Default")
      (node (ref "IC1") (pin "43") (pinfunction "CDBUS4_43") (pintype "bidirectional"))
    )
    (net (code "57") (name "unconnected-(IC1-CDBUS5-Pad44)") (class "Default")
      (node (ref "IC1") (pin "44") (pinfunction "CDBUS5_44") (pintype "bidirectional"))
    )
    (net (code "58") (name "unconnected-(IC1-CDBUS6-Pad45)") (class "Default")
      (node (ref "IC1") (pin "45") (pinfunction "CDBUS6_45") (pintype "bidirectional"))
    )
    (net (code "59") (name "unconnected-(IC1-DDBUS2-Pad53)") (class "Default")
      (node (ref "IC1") (pin "53") (pinfunction "DDBUS2_53") (pintype "bidirectional"))
    )
    (net (code "60") (name "unconnected-(IC1-DDBUS3-Pad54)") (class "Default")
      (node (ref "IC1") (pin "54") (pinfunction "DDBUS3_54") (pintype "bidirectional"))
    )
    (net (code "61") (name "unconnected-(IC1-DDBUS4-Pad55)") (class "Default")
      (node (ref "IC1") (pin "55") (pinfunction "DDBUS4_55") (pintype "bidirectional"))
    )
    (net (code "62") (name "unconnected-(IC1-DDBUS5-Pad57)") (class "Default")
      (node (ref "IC1") (pin "57") (pinfunction "DDBUS5_57") (pintype "bidirectional"))
    )
    (net (code "63") (name "unconnected-(IC1-DDBUS6-Pad58)") (class "Default")
      (node (ref "IC1") (pin "58") (pinfunction "DDBUS6_58") (pintype "bidirectional"))
    )
    (net (code "64") (name "unconnected-(IC1-SUSPEND#-Pad36)") (class "Default")
      (node (ref "IC1") (pin "36") (pinfunction "SUSPEND#_36") (pintype "bidirectional"))
    )
    (net (code "65") (name "unconnected-(USB1-ID-Pad4)") (class "Default")
      (node (ref "USB1") (pin "4") (pinfunction "ID_4") (pintype "bidirectional"))
    )
  )
)
